# Total.net
KiCad netlist of a schematic drawn in Altium Designer
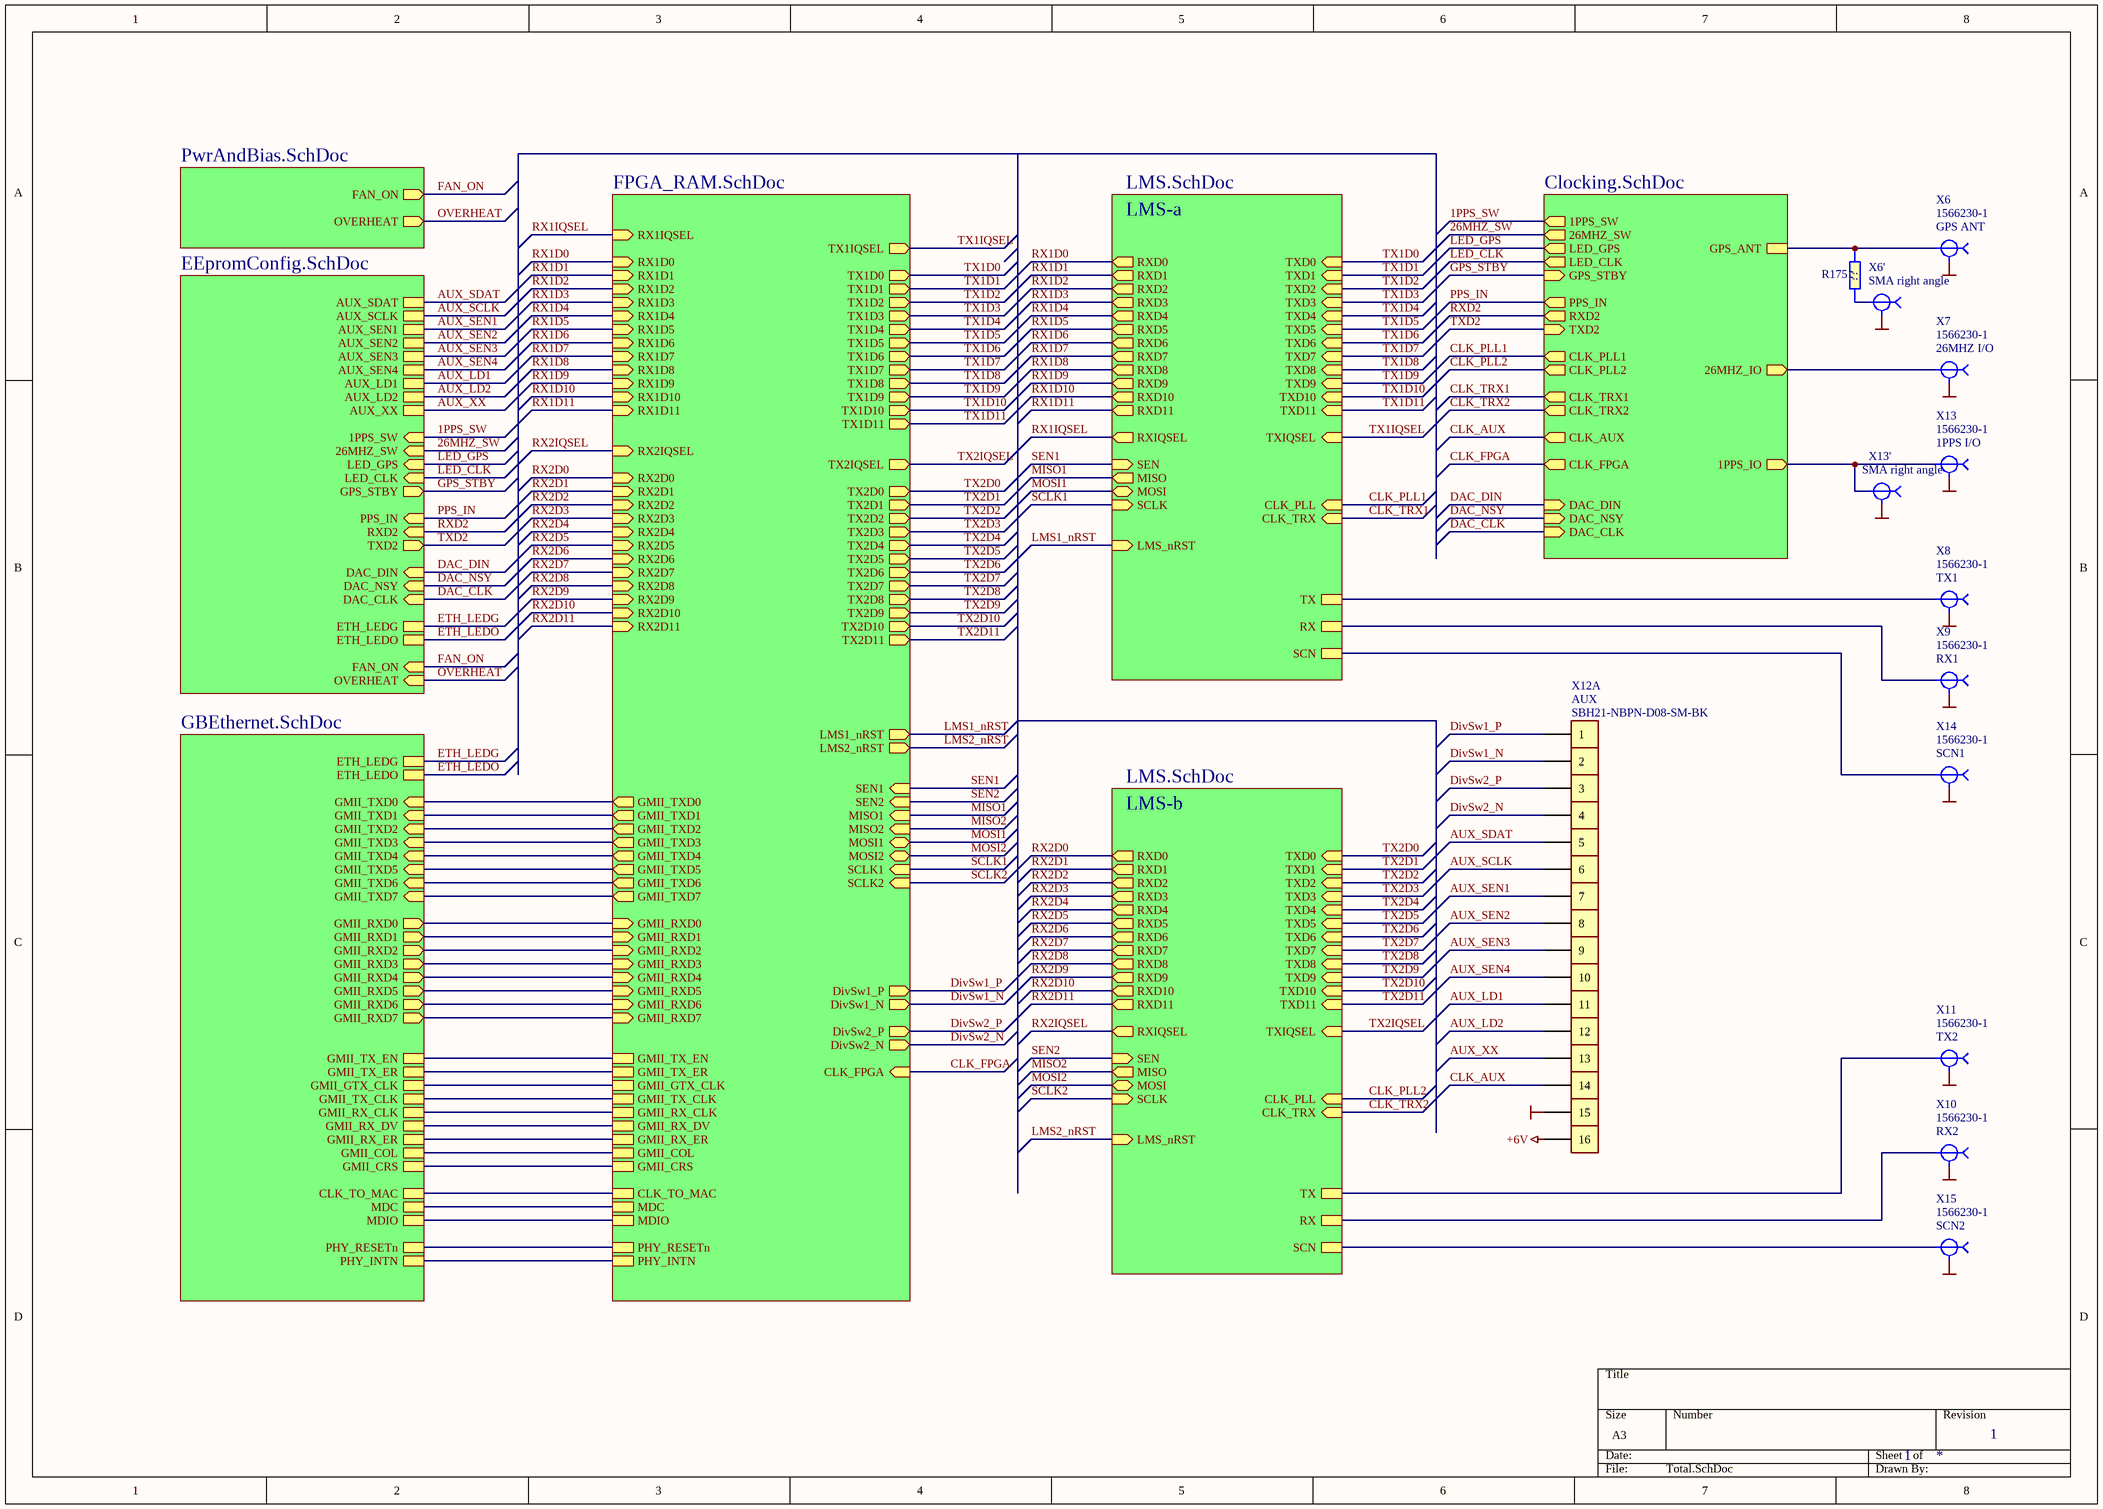
[diagram p0: Total.SchDoc]

(export (version "E")
  (design (tool "Eeschema 10.0.6"))
  (components
    (comp (ref "R175")
      (value "??")
      (footprint "R0603-PHILLIPS")
      (description "Резистор")
      (fields (field (name "MANUFACTURER") "YAGEO") (field (name "TOLERANCE") "5%"))
      (libsource (lib "altium-import") (part "root_2_R0603_"))
    )
    (comp (ref "X6")
      (value "1566230-1")
      (footprint "U_FL")
      (description "Ultraminiature Coax Connector (UMCC)")
      (fields (field (name "MANUFACTURER") "Tyco Electronics Corp") (field (name "DSCRIPTION") "GPS ANT"))
      (libsource (lib "Andy") (part "U_FL"))
    )
    (comp (ref "X6'")
      (value "SMA right angle")
      (footprint "SMA right angle")
      (description "Разъем")
      (libsource (lib "Andy") (part "SMA-Right Angle"))
    )
    (comp (ref "X7")
      (value "1566230-1")
      (footprint "U_FL")
      (description "Ultraminiature Coax Connector (UMCC)")
      (fields (field (name "MANUFACTURER") "Tyco Electronics Corp") (field (name "DSCRIPTION") "26MHZ I/O"))
      (libsource (lib "Andy") (part "U_FL"))
    )
    (comp (ref "X8")
      (value "1566230-1")
      (footprint "U_FL")
      (description "Ultraminiature Coax Connector (UMCC)")
      (fields (field (name "MANUFACTURER") "Tyco Electronics Corp") (field (name "DSCRIPTION") "TX1"))
      (libsource (lib "Andy") (part "U_FL"))
    )
    (comp (ref "X9")
      (value "1566230-1")
      (footprint "U_FL")
      (description "Ultraminiature Coax Connector (UMCC)")
      (fields (field (name "MANUFACTURER") "Tyco Electronics Corp") (field (name "DSCRIPTION") "RX1"))
      (libsource (lib "Andy") (part "U_FL"))
    )
    (comp (ref "X10")
      (value "1566230-1")
      (footprint "U_FL")
      (description "Ultraminiature Coax Connector (UMCC)")
      (fields (field (name "MANUFACTURER") "Tyco Electronics Corp") (field (name "DSCRIPTION") "RX2"))
      (libsource (lib "Andy") (part "U_FL"))
    )
    (comp (ref "X11")
      (value "1566230-1")
      (footprint "U_FL")
      (description "Ultraminiature Coax Connector (UMCC)")
      (fields (field (name "MANUFACTURER") "Tyco Electronics Corp") (field (name "DSCRIPTION") "TX2"))
      (libsource (lib "Andy") (part "U_FL"))
    )
    (comp (ref "X12")
      (value "SBH21-NBPN-D08-SM-BK")
      (footprint "SBH-16")
      (description "Connector 2mm SMD")
      (fields (field (name "MANUFACTURER") "Sullins") (field (name "MISC") "AUX"))
      (libsource (lib "Andy") (part "SBH21-8x2_SMD"))
    )
    (comp (ref "X13")
      (value "1566230-1")
      (footprint "U_FL")
      (description "Ultraminiature Coax Connector (UMCC)")
      (fields (field (name "MANUFACTURER") "Tyco Electronics Corp") (field (name "DSCRIPTION") "1PPS I/O"))
      (libsource (lib "Andy") (part "U_FL"))
    )
    (comp (ref "X13'")
      (value "SMA right angle")
      (footprint "SMA right angle")
      (description "Разъем")
      (libsource (lib "Andy") (part "SMA-Right Angle"))
    )
    (comp (ref "X14")
      (value "1566230-1")
      (footprint "U_FL")
      (description "Ultraminiature Coax Connector (UMCC)")
      (fields (field (name "MANUFACTURER") "Tyco Electronics Corp") (field (name "DSCRIPTION") "SCN1"))
      (libsource (lib "Andy") (part "U_FL"))
    )
    (comp (ref "X15")
      (value "1566230-1")
      (footprint "U_FL")
      (description "Ultraminiature Coax Connector (UMCC)")
      (fields (field (name "MANUFACTURER") "Tyco Electronics Corp") (field (name "DSCRIPTION") "SCN2"))
      (libsource (lib "Andy") (part "U_FL"))
    )
  )
  (nets
    (net (code "1") (name "+6V") (class "Default")
      (node (ref "X12") (pin "16") (pinfunction "16_16") (pintype "passive"))
    )
    (net (code "2") (name "/1PPS_IO") (class "Default")
      (node (ref "X13") (pin "1") (pinfunction "1_1") (pintype "passive"))
      (node (ref "X13'") (pin "1") (pinfunction "1_1") (pintype "passive"))
    )
    (net (code "4") (name "/26MHZ_IO") (class "Default")
      (node (ref "X7") (pin "1") (pinfunction "1_1") (pintype "passive"))
    )
    (net (code "6") (name "/AUX_LD1") (class "Default")
      (node (ref "X12") (pin "11") (pinfunction "11_11") (pintype "passive"))
    )
    (net (code "7") (name "/AUX_LD2") (class "Default")
      (node (ref "X12") (pin "12") (pinfunction "12_12") (pintype "passive"))
    )
    (net (code "8") (name "/AUX_SCLK") (class "Default")
      (node (ref "X12") (pin "6") (pinfunction "6_6") (pintype "passive"))
    )
    (net (code "9") (name "/AUX_SDAT") (class "Default")
      (node (ref "X12") (pin "5") (pinfunction "5_5") (pintype "passive"))
    )
    (net (code "10") (name "/AUX_SEN1") (class "Default")
      (node (ref "X12") (pin "7") (pinfunction "7_7") (pintype "passive"))
    )
    (net (code "11") (name "/AUX_SEN2") (class "Default")
      (node (ref "X12") (pin "8") (pinfunction "8_8") (pintype "passive"))
    )
    (net (code "12") (name "/AUX_SEN3") (class "Default")
      (node (ref "X12") (pin "9") (pinfunction "9_9") (pintype "passive"))
    )
    (net (code "13") (name "/AUX_SEN4") (class "Default")
      (node (ref "X12") (pin "10") (pinfunction "10_10") (pintype "passive"))
    )
    (net (code "14") (name "/AUX_XX") (class "Default")
      (node (ref "X12") (pin "13") (pinfunction "13_13") (pintype "passive"))
    )
    (net (code "15") (name "/CLK_AUX") (class "Default")
      (node (ref "X12") (pin "14") (pinfunction "14_14") (pintype "passive"))
    )
    (net (code "25") (name "/DivSw1_N") (class "Default")
      (node (ref "X12") (pin "2") (pinfunction "2_2") (pintype "passive"))
    )
    (net (code "26") (name "/DivSw1_P") (class "Default")
      (node (ref "X12") (pin "1") (pinfunction "1_1") (pintype "passive"))
    )
    (net (code "27") (name "/DivSw2_N") (class "Default")
      (node (ref "X12") (pin "4") (pinfunction "4_4") (pintype "passive"))
    )
    (net (code "28") (name "/DivSw2_P") (class "Default")
      (node (ref "X12") (pin "3") (pinfunction "3_3") (pintype "passive"))
    )
    (net (code "57") (name "/GPS_ANT") (class "Default")
      (node (ref "R175") (pin "2") (pinfunction "2_2") (pintype "passive"))
      (node (ref "X6") (pin "1") (pinfunction "1_1") (pintype "passive"))
    )
    (net (code "73") (name "/RX") (class "Default")
      (node (ref "X10") (pin "1") (pinfunction "1_1") (pintype "passive"))
    )
    (net (code "101") (name "/RX_1") (class "Default")
      (node (ref "X9") (pin "1") (pinfunction "1_1") (pintype "passive"))
    )
    (net (code "104") (name "/SCN") (class "Default")
      (node (ref "X15") (pin "1") (pinfunction "1_1") (pintype "passive"))
    )
    (net (code "105") (name "/SCN_1") (class "Default")
      (node (ref "X14") (pin "1") (pinfunction "1_1") (pintype "passive"))
    )
    (net (code "108") (name "/TX") (class "Default")
      (node (ref "X11") (pin "1") (pinfunction "1_1") (pintype "passive"))
    )
    (net (code "136") (name "/TX_1") (class "Default")
      (node (ref "X8") (pin "1") (pinfunction "1_1") (pintype "passive"))
    )
    (net (code "137") (name "GND") (class "Default")
      (node (ref "X10") (pin "2") (pinfunction "GND_2") (pintype "passive"))
      (node (ref "X11") (pin "2") (pinfunction "GND_2") (pintype "passive"))
      (node (ref "X12") (pin "15") (pinfunction "15_15") (pintype "passive"))
      (node (ref "X13") (pin "2") (pinfunction "GND_2") (pintype "passive"))
      (node (ref "X13'") (pin "2") (pinfunction "GND_2") (pintype "power_in"))
      (node (ref "X14") (pin "2") (pinfunction "GND_2") (pintype "passive"))
      (node (ref "X15") (pin "2") (pinfunction "GND_2") (pintype "passive"))
      (node (ref "X6") (pin "2") (pinfunction "GND_2") (pintype "passive"))
      (node (ref "X6'") (pin "2") (pinfunction "GND_2") (pintype "power_in"))
      (node (ref "X7") (pin "2") (pinfunction "GND_2") (pintype "passive"))
      (node (ref "X8") (pin "2") (pinfunction "GND_2") (pintype "passive"))
      (node (ref "X9") (pin "2") (pinfunction "GND_2") (pintype "passive"))
    )
    (net (code "138") (name "Net-(R175-Pad1)") (class "Default")
      (node (ref "R175") (pin "1") (pinfunction "1_1") (pintype "passive"))
      (node (ref "X6'") (pin "1") (pinfunction "1_1") (pintype "passive"))
    )
  )
)
